# adc_dac_rxd.net
KiCad netlist of a schematic drawn in Altium Designer
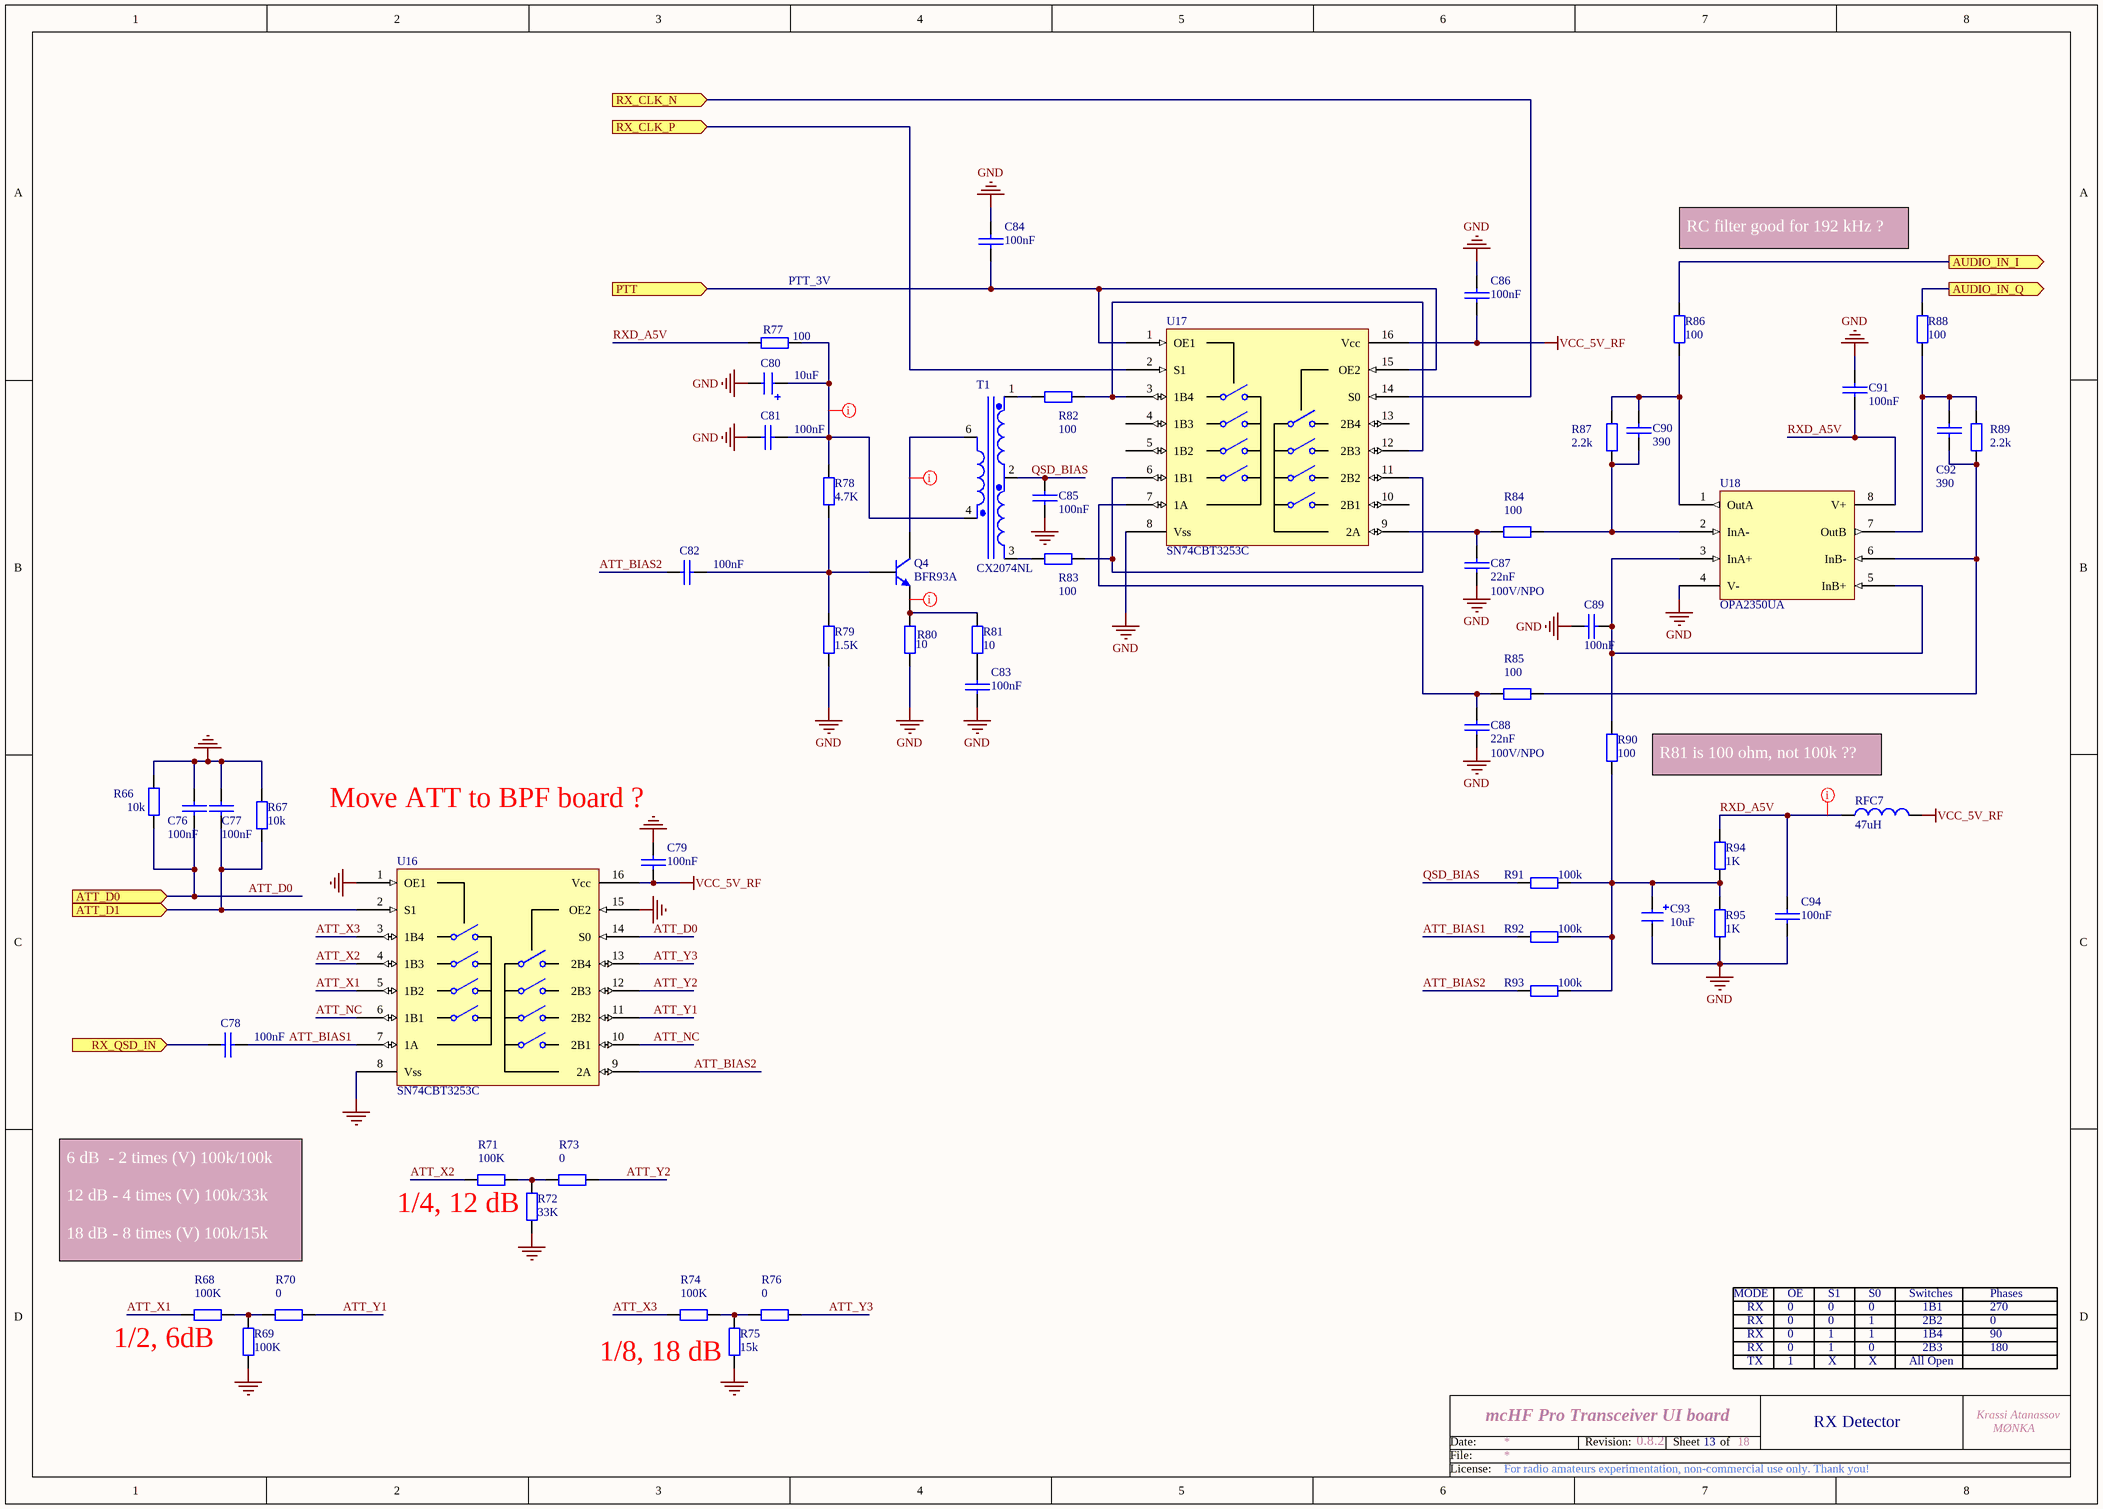
[diagram p0: adc_dac_rxd.SchDoc]

(export (version "E")
  (design (tool "Eeschema 10.0.6"))
  (components
    (comp (ref "C76")
      (value "100nF")
      (footprint "0805")
      (description "Capacitor")
      (libsource (lib "mcHF_rf") (part "CAP"))
    )
    (comp (ref "C77")
      (value "100nF")
      (footprint "0805")
      (description "Capacitor")
      (libsource (lib "mcHF_rf") (part "CAP"))
    )
    (comp (ref "C78")
      (value "100nF")
      (footprint "0805")
      (description "Capacitor")
      (libsource (lib "mcHF_rf") (part "CAP"))
    )
    (comp (ref "C79")
      (value "100nF")
      (footprint "0805")
      (description "Capacitor")
      (libsource (lib "mcHF_rf") (part "CAP"))
    )
    (comp (ref "C80")
      (value "10uF")
      (footprint "1206_Elec_Cap")
      (description "Electrolitic capacitor")
      (libsource (lib "mcHF_rf") (part "CAP-POL"))
    )
    (comp (ref "C81")
      (value "100nF")
      (footprint "0805")
      (description "Capacitor")
      (libsource (lib "mcHF_rf") (part "CAP"))
    )
    (comp (ref "C82")
      (value "100nF")
      (footprint "0805")
      (description "Capacitor")
      (libsource (lib "mcHF_rf") (part "CAP"))
    )
    (comp (ref "C83")
      (value "100nF")
      (footprint "0805")
      (description "Capacitor")
      (libsource (lib "mcHF_rf") (part "CAP"))
    )
    (comp (ref "C84")
      (value "100nF")
      (footprint "0805")
      (description "Capacitor")
      (libsource (lib "mcHF_rf") (part "CAP"))
    )
    (comp (ref "C85")
      (value "100nF")
      (footprint "0805")
      (description "Capacitor")
      (libsource (lib "mcHF_rf") (part "CAP"))
    )
    (comp (ref "C86")
      (value "100nF")
      (footprint "0805")
      (description "Capacitor")
      (libsource (lib "mcHF_rf") (part "CAP"))
    )
    (comp (ref "C87")
      (value "22nF")
      (footprint "CAP_B")
      (description "Capacitor")
      (fields (field (name "VOLTAGE") "100V/NPO"))
      (libsource (lib "mcHF_rf") (part "CAP"))
    )
    (comp (ref "C88")
      (value "22nF")
      (footprint "CAP_B")
      (description "Capacitor")
      (fields (field (name "VOLTAGE") "100V/NPO"))
      (libsource (lib "mcHF_rf") (part "CAP"))
    )
    (comp (ref "C89")
      (value "100nF")
      (footprint "0805")
      (description "Capacitor")
      (libsource (lib "mcHF_rf") (part "CAP"))
    )
    (comp (ref "C90")
      (value "390")
      (footprint "0805")
      (description "Capacitor")
      (libsource (lib "mcHF_rf") (part "CAP"))
    )
    (comp (ref "C91")
      (value "100nF")
      (footprint "0805")
      (description "Capacitor")
      (libsource (lib "mcHF_rf") (part "CAP"))
    )
    (comp (ref "C92")
      (value "390")
      (footprint "0805")
      (description "Capacitor")
      (libsource (lib "mcHF_rf") (part "CAP"))
    )
    (comp (ref "C93")
      (value "10uF")
      (footprint "1206_Elec_Cap")
      (description "Electrolitic capacitor")
      (libsource (lib "mcHF_rf") (part "CAP-POL"))
    )
    (comp (ref "C94")
      (value "100nF")
      (footprint "0805")
      (description "Capacitor")
      (libsource (lib "mcHF_rf") (part "CAP"))
    )
    (comp (ref "Q4")
      (value "BFR93A")
      (footprint "SOT-23")
      (description "TRANSISTOR, RF, NPN, 12V, 0.035MA,SOT-23")
      (libsource (lib "mcHF_rf") (part "BFR93A"))
    )
    (comp (ref "R66")
      (value "10k")
      (footprint "0805")
      (description "Resistor")
      (libsource (lib "mcHF_ui_b") (part "RES"))
    )
    (comp (ref "R67")
      (value "10k")
      (footprint "0805")
      (description "Resistor")
      (libsource (lib "mcHF_ui_b") (part "RES"))
    )
    (comp (ref "R68")
      (value "100K")
      (footprint "0805")
      (description "Resistor")
      (libsource (lib "") (part "RES_1"))
    )
    (comp (ref "R69")
      (value "100K")
      (footprint "0805")
      (description "Resistor")
      (libsource (lib "mcHF_rf") (part "RES"))
    )
    (comp (ref "R70")
      (value "0")
      (footprint "0805")
      (description "Resistor")
      (libsource (lib "") (part "RES_1"))
    )
    (comp (ref "R71")
      (value "100K")
      (footprint "0805")
      (description "Resistor")
      (libsource (lib "") (part "RES_1"))
    )
    (comp (ref "R72")
      (value "33K")
      (footprint "0805")
      (description "Resistor")
      (libsource (lib "mcHF_rf") (part "RES"))
    )
    (comp (ref "R73")
      (value "0")
      (footprint "0805")
      (description "Resistor")
      (libsource (lib "") (part "RES_1"))
    )
    (comp (ref "R74")
      (value "100K")
      (footprint "0805")
      (description "Resistor")
      (libsource (lib "") (part "RES_1"))
    )
    (comp (ref "R75")
      (value "15k")
      (footprint "0805")
      (description "Resistor")
      (libsource (lib "mcHF_rf") (part "RES"))
    )
    (comp (ref "R76")
      (value "0")
      (footprint "0805")
      (description "Resistor")
      (libsource (lib "") (part "RES_1"))
    )
    (comp (ref "R77")
      (value "100")
      (footprint "0805")
      (description "Resistor")
      (libsource (lib "") (part "RES_1"))
    )
    (comp (ref "R78")
      (value "4.7K")
      (footprint "0805")
      (description "Resistor")
      (libsource (lib "") (part "RES_3"))
    )
    (comp (ref "R79")
      (value "1.5K")
      (footprint "0805")
      (description "Resistor")
      (libsource (lib "") (part "RES_3"))
    )
    (comp (ref "R80")
      (value "10")
      (footprint "0805")
      (description "Resistor")
      (libsource (lib "mcHF_rf") (part "RES"))
    )
    (comp (ref "R81")
      (value "10")
      (footprint "0805")
      (description "Resistor")
      (libsource (lib "mcHF_rf") (part "RES"))
    )
    (comp (ref "R82")
      (value "100")
      (footprint "0805")
      (description "Resistor")
      (libsource (lib "") (part "RES_1"))
    )
    (comp (ref "R83")
      (value "100")
      (footprint "0805")
      (description "Resistor")
      (libsource (lib "") (part "RES_1"))
    )
    (comp (ref "R84")
      (value "100")
      (footprint "0805")
      (description "Resistor")
      (libsource (lib "") (part "RES_1"))
    )
    (comp (ref "R85")
      (value "100")
      (footprint "0805")
      (description "Resistor")
      (libsource (lib "") (part "RES_1"))
    )
    (comp (ref "R86")
      (value "100")
      (footprint "0805")
      (description "Resistor")
      (libsource (lib "mcHF_rf") (part "RES"))
    )
    (comp (ref "R87")
      (value "2.2k")
      (footprint "0805")
      (description "Resistor")
      (libsource (lib "mcHF_rf") (part "RES"))
    )
    (comp (ref "R88")
      (value "100")
      (footprint "0805")
      (description "Resistor")
      (libsource (lib "mcHF_rf") (part "RES"))
    )
    (comp (ref "R89")
      (value "2.2k")
      (footprint "0805")
      (description "Resistor")
      (libsource (lib "mcHF_rf") (part "RES"))
    )
    (comp (ref "R90")
      (value "100")
      (footprint "0805")
      (description "Resistor")
      (libsource (lib "mcHF_rf") (part "RES"))
    )
    (comp (ref "R91")
      (value "100k")
      (footprint "0805")
      (description "Resistor")
      (libsource (lib "") (part "RES_2"))
    )
    (comp (ref "R92")
      (value "100k")
      (footprint "0805")
      (description "Resistor")
      (libsource (lib "") (part "RES_1"))
    )
    (comp (ref "R93")
      (value "100k")
      (footprint "0805")
      (description "Resistor")
      (libsource (lib "") (part "RES_1"))
    )
    (comp (ref "R94")
      (value "1K")
      (footprint "0805")
      (description "Resistor")
      (libsource (lib "mcHF_rf") (part "RES"))
    )
    (comp (ref "R95")
      (value "1K")
      (footprint "0805")
      (description "Resistor")
      (libsource (lib "mcHF_rf") (part "RES"))
    )
    (comp (ref "RFC7")
      (value "47uH")
      (footprint "0805")
      (description "INDUCTOR, SIGNAL LINE, 4.7UH, 1005")
      (libsource (lib "mcHF_rf") (part "TDK-NLV25T"))
    )
    (comp (ref "T1")
      (value "CX2074NL")
      (footprint "SOP5_NEW1")
      (description "Wideband RF Transformer 1:4")
      (libsource (lib "mcHF_rf") (part "CX2074NL"))
    )
    (comp (ref "U16")
      (value "SN74CBT3253C")
      (footprint "SO-16-Pro")
      (description "Dual 4:1 Demux/Analog Switch")
      (libsource (lib "mcHF_rf") (part "SN74CBT3253C"))
    )
    (comp (ref "U17")
      (value "SN74CBT3253C")
      (footprint "SO-16-Pro")
      (description "Dual 4:1 Demux/Analog Switch")
      (libsource (lib "mcHF_rf") (part "SN74CBT3253C"))
    )
    (comp (ref "U18")
      (value "OPA2350UA")
      (footprint "SO-8")
      (description "High Speed, Single Supply OpAmp")
      (libsource (lib "mcHF_rf") (part "OPA2350UA"))
    )
  )
  (nets
    (net (code "1") (name "/ATT_BIAS1") (class "Default")
      (node (ref "C78") (pin "1") (pinfunction "1_1") (pintype "passive"))
      (node (ref "R92") (pin "1") (pinfunction "1_1") (pintype "passive"))
      (node (ref "U16") (pin "7") (pinfunction "1A_7") (pintype "bidirectional"))
    )
    (net (code "2") (name "/ATT_BIAS2") (class "Default")
      (node (ref "C82") (pin "2") (pinfunction "2_2") (pintype "passive"))
      (node (ref "R93") (pin "1") (pinfunction "1_1") (pintype "passive"))
      (node (ref "U16") (pin "9") (pinfunction "2A_9") (pintype "bidirectional"))
    )
    (net (code "3") (name "/ATT_D0") (class "Default")
      (node (ref "C76") (pin "1") (pinfunction "1_1") (pintype "passive"))
      (node (ref "R66") (pin "2") (pinfunction "2_2") (pintype "passive"))
      (node (ref "U16") (pin "14") (pinfunction "S0_14") (pintype "input"))
    )
    (net (code "4") (name "/ATT_D1") (class "Default")
      (node (ref "C77") (pin "1") (pinfunction "1_1") (pintype "passive"))
      (node (ref "R67") (pin "2") (pinfunction "2_2") (pintype "passive"))
      (node (ref "U16") (pin "2") (pinfunction "S1_2") (pintype "input"))
    )
    (net (code "5") (name "/ATT_NC") (class "Default")
      (node (ref "U16") (pin "10") (pinfunction "2B1_10") (pintype "bidirectional"))
      (node (ref "U16") (pin "6") (pinfunction "1B1_6") (pintype "bidirectional"))
    )
    (net (code "6") (name "/ATT_X1") (class "Default")
      (node (ref "R68") (pin "1") (pinfunction "1_1") (pintype "passive"))
      (node (ref "U16") (pin "5") (pinfunction "1B2_5") (pintype "bidirectional"))
    )
    (net (code "7") (name "/ATT_X2") (class "Default")
      (node (ref "R71") (pin "1") (pinfunction "1_1") (pintype "passive"))
      (node (ref "U16") (pin "4") (pinfunction "1B3_4") (pintype "bidirectional"))
    )
    (net (code "8") (name "/ATT_X3") (class "Default")
      (node (ref "R74") (pin "1") (pinfunction "1_1") (pintype "passive"))
      (node (ref "U16") (pin "3") (pinfunction "1B4_3") (pintype "bidirectional"))
    )
    (net (code "9") (name "/ATT_Y1") (class "Default")
      (node (ref "R70") (pin "2") (pinfunction "2_2") (pintype "passive"))
      (node (ref "U16") (pin "11") (pinfunction "2B2_11") (pintype "bidirectional"))
    )
    (net (code "10") (name "/ATT_Y2") (class "Default")
      (node (ref "R73") (pin "2") (pinfunction "2_2") (pintype "passive"))
      (node (ref "U16") (pin "12") (pinfunction "2B3_12") (pintype "bidirectional"))
    )
    (net (code "11") (name "/ATT_Y3") (class "Default")
      (node (ref "R76") (pin "2") (pinfunction "2_2") (pintype "passive"))
      (node (ref "U16") (pin "13") (pinfunction "2B4_13") (pintype "bidirectional"))
    )
    (net (code "12") (name "/AUDIO_IN_I") (class "Default")
      (node (ref "R86") (pin "2") (pinfunction "2_2") (pintype "passive"))
    )
    (net (code "13") (name "/AUDIO_IN_Q") (class "Default")
      (node (ref "R88") (pin "2") (pinfunction "2_2") (pintype "passive"))
    )
    (net (code "14") (name "/PTT") (class "Default")
      (node (ref "C84") (pin "1") (pinfunction "1_1") (pintype "passive"))
      (node (ref "U17") (pin "1") (pinfunction "OE1_1") (pintype "input"))
      (node (ref "U17") (pin "15") (pinfunction "OE2_15") (pintype "input"))
    )
    (net (code "15") (name "/QSD_BIAS") (class "Default")
      (node (ref "C85") (pin "1") (pinfunction "1_1") (pintype "passive"))
      (node (ref "R91") (pin "2") (pinfunction "2_2") (pintype "passive"))
      (node (ref "T1") (pin "2") (pinfunction "SecCmn_2") (pintype "passive"))
    )
    (net (code "16") (name "/RXD_A5V") (class "Default")
      (node (ref "C91") (pin "2") (pinfunction "2_2") (pintype "passive"))
      (node (ref "C94") (pin "2") (pinfunction "2_2") (pintype "passive"))
      (node (ref "R77") (pin "1") (pinfunction "1_1") (pintype "passive"))
      (node (ref "R94") (pin "2") (pinfunction "2_2") (pintype "passive"))
      (node (ref "RFC7") (pin "1") (pinfunction "1_1") (pintype "passive"))
      (node (ref "U18") (pin "8") (pinfunction "V+_8") (pintype "power_in"))
    )
    (net (code "17") (name "/RX_CLK_N") (class "Default")
      (node (ref "U17") (pin "14") (pinfunction "S0_14") (pintype "input"))
    )
    (net (code "18") (name "/RX_CLK_P") (class "Default")
      (node (ref "U17") (pin "2") (pinfunction "S1_2") (pintype "input"))
    )
    (net (code "19") (name "/RX_QSD_IN") (class "Default")
      (node (ref "C78") (pin "2") (pinfunction "2_2") (pintype "passive"))
    )
    (net (code "20") (name "GND") (class "Default")
      (node (ref "C76") (pin "2") (pinfunction "2_2") (pintype "passive"))
      (node (ref "C77") (pin "2") (pinfunction "2_2") (pintype "passive"))
      (node (ref "C79") (pin "2") (pinfunction "2_2") (pintype "passive"))
      (node (ref "C80") (pin "2") (pinfunction "2_2") (pintype "passive"))
      (node (ref "C81") (pin "2") (pinfunction "2_2") (pintype "passive"))
      (node (ref "C83") (pin "1") (pinfunction "1_1") (pintype "passive"))
      (node (ref "C84") (pin "2") (pinfunction "2_2") (pintype "passive"))
      (node (ref "C85") (pin "2") (pinfunction "2_2") (pintype "passive"))
      (node (ref "C86") (pin "2") (pinfunction "2_2") (pintype "passive"))
      (node (ref "C87") (pin "2") (pinfunction "2_2") (pintype "passive"))
      (node (ref "C88") (pin "2") (pinfunction "2_2") (pintype "passive"))
      (node (ref "C89") (pin "2") (pinfunction "2_2") (pintype "passive"))
      (node (ref "C91") (pin "1") (pinfunction "1_1") (pintype "passive"))
      (node (ref "C93") (pin "2") (pinfunction "2_2") (pintype "passive"))
      (node (ref "C94") (pin "1") (pinfunction "1_1") (pintype "passive"))
      (node (ref "R66") (pin "1") (pinfunction "1_1") (pintype "passive"))
      (node (ref "R67") (pin "1") (pinfunction "1_1") (pintype "passive"))
      (node (ref "R69") (pin "1") (pinfunction "1_1") (pintype "passive"))
      (node (ref "R72") (pin "1") (pinfunction "1_1") (pintype "passive"))
      (node (ref "R75") (pin "1") (pinfunction "1_1") (pintype "passive"))
      (node (ref "R79") (pin "2") (pinfunction "2_2") (pintype "passive"))
      (node (ref "R80") (pin "1") (pinfunction "1_1") (pintype "passive"))
      (node (ref "R95") (pin "1") (pinfunction "1_1") (pintype "passive"))
      (node (ref "U16") (pin "1") (pinfunction "OE1_1") (pintype "input"))
      (node (ref "U16") (pin "15") (pinfunction "OE2_15") (pintype "input"))
      (node (ref "U16") (pin "8") (pinfunction "Vss_8") (pintype "power_in"))
      (node (ref "U17") (pin "8") (pinfunction "Vss_8") (pintype "power_in"))
      (node (ref "U18") (pin "4") (pinfunction "V-_4") (pintype "power_in"))
    )
    (net (code "21") (name "Net-(C83-Pad2)") (class "Default")
      (node (ref "C83") (pin "2") (pinfunction "2_2") (pintype "passive"))
      (node (ref "R81") (pin "1") (pinfunction "1_1") (pintype "passive"))
    )
    (net (code "22") (name "Net-(C93-Pad1)") (class "Default")
      (node (ref "C93") (pin "1") (pinfunction "1_1") (pintype "passive"))
      (node (ref "R90") (pin "1") (pinfunction "1_1") (pintype "passive"))
      (node (ref "R91") (pin "1") (pinfunction "1_1") (pintype "passive"))
      (node (ref "R92") (pin "2") (pinfunction "2_2") (pintype "passive"))
      (node (ref "R93") (pin "2") (pinfunction "2_2") (pintype "passive"))
      (node (ref "R94") (pin "1") (pinfunction "1_1") (pintype "passive"))
      (node (ref "R95") (pin "2") (pinfunction "2_2") (pintype "passive"))
    )
    (net (code "23") (name "Net-(Q4-B)") (class "Default")
      (node (ref "C82") (pin "1") (pinfunction "1_1") (pintype "passive"))
      (node (ref "Q4") (pin "1") (pinfunction "B_1") (pintype "passive"))
      (node (ref "R78") (pin "2") (pinfunction "2_2") (pintype "passive"))
      (node (ref "R79") (pin "1") (pinfunction "1_1") (pintype "passive"))
    )
    (net (code "24") (name "Net-(Q4-C)") (class "Default")
      (node (ref "Q4") (pin "3") (pinfunction "C_3") (pintype "passive"))
      (node (ref "T1") (pin "6") (pinfunction "Pri+_6") (pintype "passive"))
    )
    (net (code "25") (name "Net-(Q4-E)") (class "Default")
      (node (ref "Q4") (pin "2") (pinfunction "E_2") (pintype "passive"))
      (node (ref "R80") (pin "2") (pinfunction "2_2") (pintype "passive"))
      (node (ref "R81") (pin "2") (pinfunction "2_2") (pintype "passive"))
    )
    (net (code "26") (name "Net-(R68-Pad2)") (class "Default")
      (node (ref "R68") (pin "2") (pinfunction "2_2") (pintype "passive"))
      (node (ref "R69") (pin "2") (pinfunction "2_2") (pintype "passive"))
      (node (ref "R70") (pin "1") (pinfunction "1_1") (pintype "passive"))
    )
    (net (code "27") (name "Net-(R71-Pad2)") (class "Default")
      (node (ref "R71") (pin "2") (pinfunction "2_2") (pintype "passive"))
      (node (ref "R72") (pin "2") (pinfunction "2_2") (pintype "passive"))
      (node (ref "R73") (pin "1") (pinfunction "1_1") (pintype "passive"))
    )
    (net (code "28") (name "Net-(R74-Pad2)") (class "Default")
      (node (ref "R74") (pin "2") (pinfunction "2_2") (pintype "passive"))
      (node (ref "R75") (pin "2") (pinfunction "2_2") (pintype "passive"))
      (node (ref "R76") (pin "1") (pinfunction "1_1") (pintype "passive"))
    )
    (net (code "29") (name "Net-(T1-Pri-)") (class "Default")
      (node (ref "C80") (pin "1") (pinfunction "1_1") (pintype "passive"))
      (node (ref "C81") (pin "1") (pinfunction "1_1") (pintype "passive"))
      (node (ref "R77") (pin "2") (pinfunction "2_2") (pintype "passive"))
      (node (ref "R78") (pin "1") (pinfunction "1_1") (pintype "passive"))
      (node (ref "T1") (pin "4") (pinfunction "Pri-_4") (pintype "passive"))
    )
    (net (code "30") (name "Net-(T1-Sec0)") (class "Default")
      (node (ref "R82") (pin "1") (pinfunction "1_1") (pintype "passive"))
      (node (ref "T1") (pin "1") (pinfunction "Sec0_1") (pintype "passive"))
    )
    (net (code "31") (name "Net-(T1-Sec180)") (class "Default")
      (node (ref "R83") (pin "1") (pinfunction "1_1") (pintype "passive"))
      (node (ref "T1") (pin "3") (pinfunction "Sec180_3") (pintype "passive"))
    )
    (net (code "32") (name "Net-(U17-1A)") (class "Default")
      (node (ref "C88") (pin "1") (pinfunction "1_1") (pintype "passive"))
      (node (ref "R85") (pin "1") (pinfunction "1_1") (pintype "passive"))
      (node (ref "U17") (pin "7") (pinfunction "1A_7") (pintype "bidirectional"))
    )
    (net (code "33") (name "Net-(U17-1B1)") (class "Default")
      (node (ref "R83") (pin "2") (pinfunction "2_2") (pintype "passive"))
      (node (ref "U17") (pin "11") (pinfunction "2B2_11") (pintype "bidirectional"))
      (node (ref "U17") (pin "6") (pinfunction "1B1_6") (pintype "bidirectional"))
    )
    (net (code "34") (name "Net-(U17-1B4)") (class "Default")
      (node (ref "R82") (pin "2") (pinfunction "2_2") (pintype "passive"))
      (node (ref "U17") (pin "12") (pinfunction "2B3_12") (pintype "bidirectional"))
      (node (ref "U17") (pin "3") (pinfunction "1B4_3") (pintype "bidirectional"))
    )
    (net (code "35") (name "Net-(U17-2A)") (class "Default")
      (node (ref "C87") (pin "1") (pinfunction "1_1") (pintype "passive"))
      (node (ref "R84") (pin "1") (pinfunction "1_1") (pintype "passive"))
      (node (ref "U17") (pin "9") (pinfunction "2A_9") (pintype "bidirectional"))
    )
    (net (code "36") (name "Net-(U18-InA+)") (class "Default")
      (node (ref "C89") (pin "1") (pinfunction "1_1") (pintype "passive"))
      (node (ref "R90") (pin "2") (pinfunction "2_2") (pintype "passive"))
      (node (ref "U18") (pin "3") (pinfunction "InA+_3") (pintype "input"))
      (node (ref "U18") (pin "5") (pinfunction "InB+_5") (pintype "input"))
    )
    (net (code "37") (name "Net-(U18-InA-)") (class "Default")
      (node (ref "C90") (pin "1") (pinfunction "1_1") (pintype "passive"))
      (node (ref "R84") (pin "2") (pinfunction "2_2") (pintype "passive"))
      (node (ref "R87") (pin "1") (pinfunction "1_1") (pintype "passive"))
      (node (ref "U18") (pin "2") (pinfunction "InA-_2") (pintype "input"))
    )
    (net (code "38") (name "Net-(U18-InB-)") (class "Default")
      (node (ref "C92") (pin "1") (pinfunction "1_1") (pintype "passive"))
      (node (ref "R85") (pin "2") (pinfunction "2_2") (pintype "passive"))
      (node (ref "R89") (pin "1") (pinfunction "1_1") (pintype "passive"))
      (node (ref "U18") (pin "6") (pinfunction "InB-_6") (pintype "input"))
    )
    (net (code "39") (name "Net-(U18-OutA)") (class "Default")
      (node (ref "C90") (pin "2") (pinfunction "2_2") (pintype "passive"))
      (node (ref "R86") (pin "1") (pinfunction "1_1") (pintype "passive"))
      (node (ref "R87") (pin "2") (pinfunction "2_2") (pintype "passive"))
      (node (ref "U18") (pin "1") (pinfunction "OutA_1") (pintype "output"))
    )
    (net (code "40") (name "Net-(U18-OutB)") (class "Default")
      (node (ref "C92") (pin "2") (pinfunction "2_2") (pintype "passive"))
      (node (ref "R88") (pin "1") (pinfunction "1_1") (pintype "passive"))
      (node (ref "R89") (pin "2") (pinfunction "2_2") (pintype "passive"))
      (node (ref "U18") (pin "7") (pinfunction "OutB_7") (pintype "output"))
    )
    (net (code "41") (name "VCC_5V_RF") (class "Default")
      (node (ref "C79") (pin "1") (pinfunction "1_1") (pintype "passive"))
      (node (ref "C86") (pin "1") (pinfunction "1_1") (pintype "passive"))
      (node (ref "RFC7") (pin "2") (pinfunction "2_2") (pintype "passive"))
      (node (ref "U16") (pin "16") (pinfunction "Vcc_16") (pintype "power_in"))
      (node (ref "U17") (pin "16") (pinfunction "Vcc_16") (pintype "power_in"))
    )
    (net (code "42") (name "unconnected-(U17-1B2-Pad5)") (class "Default")
      (node (ref "U17") (pin "5") (pinfunction "1B2_5") (pintype "bidirectional"))
    )
    (net (code "43") (name "unconnected-(U17-1B3-Pad4)") (class "Default")
      (node (ref "U17") (pin "4") (pinfunction "1B3_4") (pintype "bidirectional"))
    )
    (net (code "44") (name "unconnected-(U17-2B1-Pad10)") (class "Default")
      (node (ref "U17") (pin "10") (pinfunction "2B1_10") (pintype "bidirectional"))
    )
    (net (code "45") (name "unconnected-(U17-2B4-Pad13)") (class "Default")
      (node (ref "U17") (pin "13") (pinfunction "2B4_13") (pintype "bidirectional"))
    )
  )
)
